# SCH_Main_board_2023-06-05.net
KiCad netlist of a schematic drawn in EasyEDA
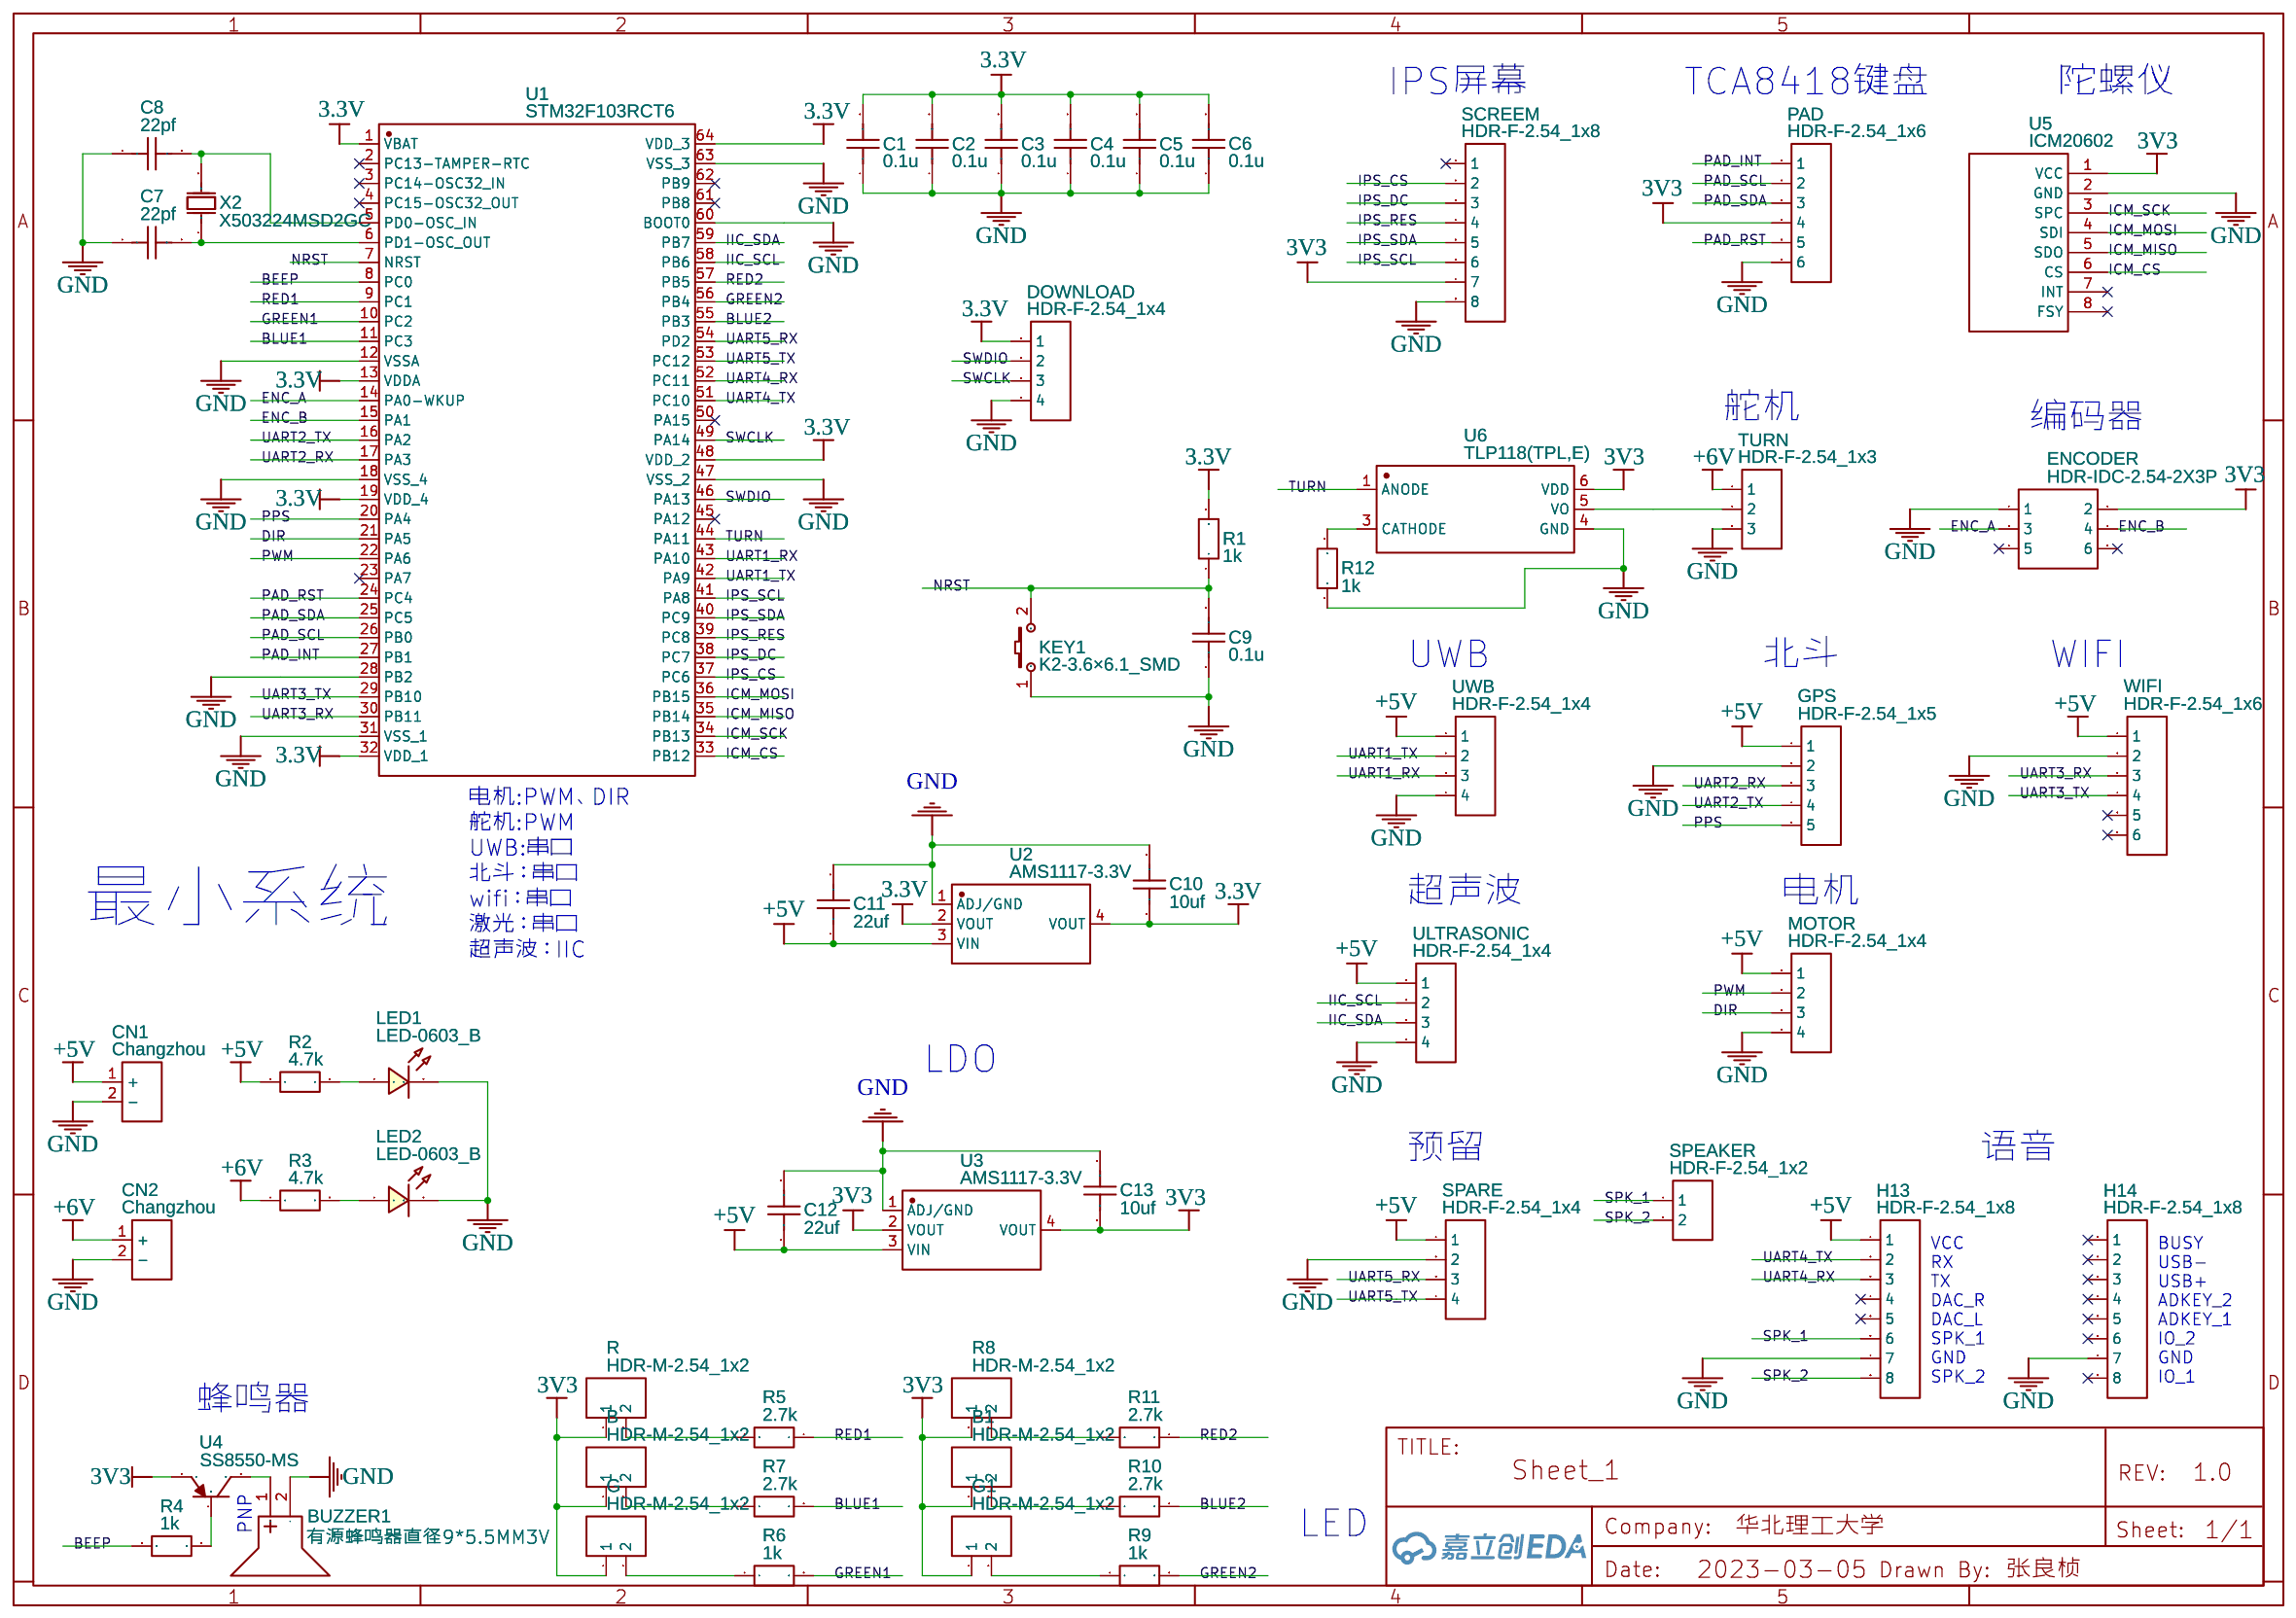
[diagram p0: schematic sheet]

(export (version "E")
  (design (tool "Eeschema 10.0.6"))
  (components
    (comp (ref "B")
      (value "HDR-M-2.54_1x2")
      (fields (field (name "BOM_Supplier Part") "C124375"))
      (libsource (lib "") (part "HDR-M-2.54_1x2_1"))
    )
    (comp (ref "B1")
      (value "HDR-M-2.54_1x2")
      (fields (field (name "BOM_Supplier Part") "C124375"))
      (libsource (lib "") (part "HDR-M-2.54_1x2_1"))
    )
    (comp (ref "BUZZER1")
      (value "有源蜂鸣器直径9*5.5MM3V")
      (fields
        (field (name "BOM_Manufacturer Part") "有源蜂鸣器直径9*5.5mm3V")
        (field (name "BOM_Supplier Part") "C9900012728")
      )
      (libsource (lib "") (part "有源蜂鸣器直径9*5.5MM3V"))
    )
    (comp (ref "C1") (value "0.1u") (libsource (lib "") (part "C_0603_US")))
    (comp (ref "C2") (value "0.1u") (libsource (lib "") (part "C_0603_US")))
    (comp (ref "C3") (value "0.1u") (libsource (lib "") (part "C_0603_US")))
    (comp (ref "C4") (value "0.1u") (libsource (lib "") (part "C_0603_US")))
    (comp (ref "C5") (value "0.1u") (libsource (lib "") (part "C_0603_US")))
    (comp (ref "C6") (value "0.1u") (libsource (lib "") (part "C_0603_US")))
    (comp (ref "C7") (value "22pf") (libsource (lib "") (part "C_0603_US_1")))
    (comp (ref "C8") (value "22pf") (libsource (lib "") (part "C_0603_US_1")))
    (comp (ref "C9") (value "0.1u") (libsource (lib "") (part "C_0603_US")))
    (comp (ref "C10") (value "10uf") (libsource (lib "") (part "C_0805_US")))
    (comp (ref "C11") (value "22uf") (libsource (lib "") (part "C_0805_US_1")))
    (comp (ref "C12") (value "22uf") (libsource (lib "") (part "C_0805_US_1")))
    (comp (ref "C13") (value "10uf") (libsource (lib "") (part "C_0805_US")))
    (comp (ref "CN1")
      (value "Changzhou")
      (fields
        (field (name "BOM_Manufacturer Part") "XT30UPB30-F.G.*")
        (field (name "BOM_Supplier Part") "C108769")
      )
      (libsource (lib "") (part "XT30UPB-F"))
    )
    (comp (ref "CN2")
      (value "Changzhou")
      (fields
        (field (name "BOM_Manufacturer Part") "XT30UPB30-F.G.*")
        (field (name "BOM_Supplier Part") "C108769")
      )
      (libsource (lib "") (part "XT30UPB-F"))
    )
    (comp (ref "DOWNLOAD")
      (value "HDR-F-2.54_1x4")
      (fields (field (name "BOM_Supplier Part") "C225501"))
      (libsource (lib "") (part "HDR-F-2.54_1x4"))
    )
    (comp (ref "ENCODER")
      (value "HDR-IDC-2.54-2X3P")
      (fields
        (field (name "BOM_Manufacturer Part") "2X3 2.54mm IDC Box")
        (field (name "BOM_Supplier Part") "C11214")
      )
      (libsource (lib "") (part "HDR-IDC-2.54-2X3P"))
    )
    (comp (ref "G")
      (value "HDR-M-2.54_1x2")
      (fields (field (name "BOM_Supplier Part") "C124375"))
      (libsource (lib "") (part "HDR-M-2.54_1x2_2"))
    )
    (comp (ref "G1")
      (value "HDR-M-2.54_1x2")
      (fields (field (name "BOM_Supplier Part") "C124375"))
      (libsource (lib "") (part "HDR-M-2.54_1x2_2"))
    )
    (comp (ref "GPS")
      (value "HDR-F-2.54_1x5")
      (fields (field (name "BOM_Supplier Part") "C50950"))
      (libsource (lib "") (part "HDR-F-2.54_1x5"))
    )
    (comp (ref "H13")
      (value "HDR-F-2.54_1x8")
      (fields (field (name "BOM_Supplier Part") "C225505"))
      (libsource (lib "") (part "HDR-F-2.54_1x8_1"))
    )
    (comp (ref "H14")
      (value "HDR-F-2.54_1x8")
      (fields (field (name "BOM_Supplier Part") "C225505"))
      (libsource (lib "") (part "HDR-F-2.54_1x8_1"))
    )
    (comp (ref "KEY1")
      (value "K2-3.6×6.1_SMD")
      (fields
        (field (name "BOM_Manufacturer Part") "K2-1107ST-A4SW-06")
        (field (name "BOM_Supplier Part") "C118141")
      )
      (libsource (lib "") (part "K2-3.6×6.1_SMD"))
    )
    (comp (ref "LED1")
      (value "LED-0603_B")
      (fields
        (field (name "BOM_Manufacturer Part") "19-217/BHC-ZL1M2RY/3T")
        (field (name "BOM_Supplier Part") "C72041")
      )
      (libsource (lib "") (part "LED-0603_B"))
    )
    (comp (ref "LED2")
      (value "LED-0603_B")
      (fields
        (field (name "BOM_Manufacturer Part") "19-217/BHC-ZL1M2RY/3T")
        (field (name "BOM_Supplier Part") "C72041")
      )
      (libsource (lib "") (part "LED-0603_B"))
    )
    (comp (ref "MOTOR")
      (value "HDR-F-2.54_1x4")
      (fields (field (name "BOM_Supplier Part") "C225501"))
      (libsource (lib "") (part "HDR-F-2.54_1x4_4"))
    )
    (comp (ref "PAD")
      (value "HDR-F-2.54_1x6")
      (fields (field (name "BOM_Supplier Part") "C40877"))
      (libsource (lib "") (part "HDR-F-2.54_1x6"))
    )
    (comp (ref "R")
      (value "HDR-M-2.54_1x2")
      (fields (field (name "BOM_Supplier Part") "C124375"))
      (libsource (lib "") (part "HDR-M-2.54_1x2"))
    )
    (comp (ref "R1") (value "1k") (libsource (lib "") (part "R_0603_EU_2")))
    (comp (ref "R2") (value "4.7k") (libsource (lib "") (part "R_0603_EU")))
    (comp (ref "R3") (value "4.7k") (libsource (lib "") (part "R_0603_EU")))
    (comp (ref "R4") (value "1k") (libsource (lib "") (part "R_0603_EU")))
    (comp (ref "R5") (value "2.7k") (libsource (lib "") (part "R_0603_EU_1")))
    (comp (ref "R6") (value "1k") (libsource (lib "") (part "R_0603_EU")))
    (comp (ref "R7") (value "2.7k") (libsource (lib "") (part "R_0603_EU")))
    (comp (ref "R8")
      (value "HDR-M-2.54_1x2")
      (fields (field (name "BOM_Supplier Part") "C124375"))
      (libsource (lib "") (part "HDR-M-2.54_1x2"))
    )
    (comp (ref "R9") (value "1k") (libsource (lib "") (part "R_0603_EU")))
    (comp (ref "R10") (value "2.7k") (libsource (lib "") (part "R_0603_EU")))
    (comp (ref "R11") (value "2.7k") (libsource (lib "") (part "R_0603_EU_1")))
    (comp (ref "R12") (value "1k") (libsource (lib "") (part "R_0603_EU_2")))
    (comp (ref "SCREEM")
      (value "HDR-F-2.54_1x8")
      (fields (field (name "BOM_Supplier Part") "C225505"))
      (libsource (lib "") (part "HDR-F-2.54_1x8"))
    )
    (comp (ref "SPARE")
      (value "HDR-F-2.54_1x4")
      (fields (field (name "BOM_Supplier Part") "C225501"))
      (libsource (lib "") (part "HDR-F-2.54_1x4_3"))
    )
    (comp (ref "SPEAKER")
      (value "HDR-F-2.54_1x2")
      (fields (field (name "BOM_Supplier Part") "C49661"))
      (libsource (lib "") (part "HDR-F-2.54_1x2"))
    )
    (comp (ref "TURN")
      (value "HDR-F-2.54_1x3")
      (fields (field (name "BOM_Supplier Part") "C146690"))
      (libsource (lib "") (part "HDR-F-2.54_1x3"))
    )
    (comp (ref "U1")
      (value "STM32F103RCT6")
      (fields (field (name "BOM_Supplier Part") "C8323"))
      (libsource (lib "") (part "STM32F103RCT6"))
    )
    (comp (ref "U2")
      (value "AMS1117-3.3V")
      (fields (field (name "BOM_Supplier Part") "C2688239"))
      (libsource (lib "") (part "AMS1117-3.3V"))
    )
    (comp (ref "U3")
      (value "AMS1117-3.3V")
      (fields (field (name "BOM_Supplier Part") "C2688239"))
      (libsource (lib "") (part "AMS1117-3.3V"))
    )
    (comp (ref "U4")
      (value "SS8550-MS")
      (fields (field (name "BOM_Supplier Part") "C5120747"))
      (libsource (lib "") (part "SS8550-MS"))
    )
    (comp (ref "U5") (value "ICM20602") (libsource (lib "") (part "ICM20602")))
    (comp (ref "U6")
      (value "TLP118(TPL,E)")
      (fields (field (name "BOM_Supplier Part") "C89721"))
      (libsource (lib "") (part "TLP118(TPL,E)"))
    )
    (comp (ref "ULTRASONIC")
      (value "HDR-F-2.54_1x4")
      (fields (field (name "BOM_Supplier Part") "C225501"))
      (libsource (lib "") (part "HDR-F-2.54_1x4_2"))
    )
    (comp (ref "UWB")
      (value "HDR-F-2.54_1x4")
      (fields (field (name "BOM_Supplier Part") "C225501"))
      (libsource (lib "") (part "HDR-F-2.54_1x4_1"))
    )
    (comp (ref "WIFI")
      (value "HDR-F-2.54_1x6")
      (fields (field (name "BOM_Supplier Part") "C40877"))
      (libsource (lib "") (part "HDR-F-2.54_1x6_1"))
    )
    (comp (ref "X2")
      (value "X503224MSD2GC")
      (fields (field (name "BOM_Supplier Part") "C48304"))
      (libsource (lib "") (part "X503224MSD2GC"))
    )
  )
  (nets
    (net (code "1") (name "+5V") (class "Default")
      (node (ref "C11") (pin "1") (pinfunction "1_1") (pintype "unspecified"))
      (node (ref "C12") (pin "1") (pinfunction "1_1") (pintype "unspecified"))
      (node (ref "CN1") (pin "1") (pinfunction "+_1") (pintype "unspecified"))
      (node (ref "GPS") (pin "1") (pinfunction "1_1") (pintype "unspecified"))
      (node (ref "H13") (pin "1") (pinfunction "1_1") (pintype "unspecified"))
      (node (ref "MOTOR") (pin "1") (pinfunction "1_1") (pintype "unspecified"))
      (node (ref "R2") (pin "1") (pinfunction "1_1") (pintype "unspecified"))
      (node (ref "SPARE") (pin "1") (pinfunction "1_1") (pintype "unspecified"))
      (node (ref "U2") (pin "3") (pinfunction "VIN_3") (pintype "unspecified"))
      (node (ref "U3") (pin "3") (pinfunction "VIN_3") (pintype "unspecified"))
      (node (ref "ULTRASONIC") (pin "1") (pinfunction "1_1") (pintype "unspecified"))
      (node (ref "UWB") (pin "1") (pinfunction "1_1") (pintype "unspecified"))
      (node (ref "WIFI") (pin "1") (pinfunction "1_1") (pintype "input"))
    )
    (net (code "2") (name "+6V") (class "Default")
      (node (ref "CN2") (pin "1") (pinfunction "+_1") (pintype "unspecified"))
      (node (ref "R3") (pin "1") (pinfunction "1_1") (pintype "unspecified"))
      (node (ref "TURN") (pin "1") (pinfunction "1_1") (pintype "input"))
    )
    (net (code "3") (name "/BEEP") (class "Default")
      (node (ref "R4") (pin "1") (pinfunction "1_1") (pintype "unspecified"))
      (node (ref "U1") (pin "8") (pinfunction "PC0_8") (pintype "unspecified"))
    )
    (net (code "4") (name "/BLUE1") (class "Default")
      (node (ref "R7") (pin "2") (pinfunction "2_2") (pintype "unspecified"))
      (node (ref "U1") (pin "11") (pinfunction "PC3_11") (pintype "unspecified"))
    )
    (net (code "5") (name "/BLUE2") (class "Default")
      (node (ref "R10") (pin "2") (pinfunction "2_2") (pintype "unspecified"))
      (node (ref "U1") (pin "55") (pinfunction "PB3_55") (pintype "unspecified"))
    )
    (net (code "6") (name "/DIR") (class "Default")
      (node (ref "MOTOR") (pin "3") (pinfunction "3_3") (pintype "unspecified"))
      (node (ref "U1") (pin "21") (pinfunction "PA5_21") (pintype "unspecified"))
    )
    (net (code "7") (name "/ENC_A") (class "Default")
      (node (ref "ENCODER") (pin "3") (pinfunction "3_3") (pintype "unspecified"))
      (node (ref "U1") (pin "14") (pinfunction "PA0-WKUP_14") (pintype "unspecified"))
    )
    (net (code "8") (name "/ENC_B") (class "Default")
      (node (ref "ENCODER") (pin "4") (pinfunction "4_4") (pintype "unspecified"))
      (node (ref "U1") (pin "15") (pinfunction "PA1_15") (pintype "unspecified"))
    )
    (net (code "9") (name "/GREEN1") (class "Default")
      (node (ref "R6") (pin "2") (pinfunction "2_2") (pintype "unspecified"))
      (node (ref "U1") (pin "10") (pinfunction "PC2_10") (pintype "unspecified"))
    )
    (net (code "10") (name "/GREEN2") (class "Default")
      (node (ref "R9") (pin "2") (pinfunction "2_2") (pintype "unspecified"))
      (node (ref "U1") (pin "56") (pinfunction "PB4_56") (pintype "unspecified"))
    )
    (net (code "11") (name "/ICM_CS") (class "Default")
      (node (ref "U1") (pin "33") (pinfunction "PB12_33") (pintype "unspecified"))
      (node (ref "U5") (pin "6") (pinfunction "CS_6") (pintype "unspecified"))
    )
    (net (code "12") (name "/ICM_MISO") (class "Default")
      (node (ref "U1") (pin "35") (pinfunction "PB14_35") (pintype "unspecified"))
      (node (ref "U5") (pin "5") (pinfunction "SDO_5") (pintype "unspecified"))
    )
    (net (code "13") (name "/ICM_MOSI") (class "Default")
      (node (ref "U1") (pin "36") (pinfunction "PB15_36") (pintype "unspecified"))
      (node (ref "U5") (pin "4") (pinfunction "SDI_4") (pintype "unspecified"))
    )
    (net (code "14") (name "/ICM_SCK") (class "Default")
      (node (ref "U1") (pin "34") (pinfunction "PB13_34") (pintype "unspecified"))
      (node (ref "U5") (pin "3") (pinfunction "SPC_3") (pintype "unspecified"))
    )
    (net (code "15") (name "/IIC_SCL") (class "Default")
      (node (ref "U1") (pin "58") (pinfunction "PB6_58") (pintype "unspecified"))
      (node (ref "ULTRASONIC") (pin "2") (pinfunction "2_2") (pintype "unspecified"))
    )
    (net (code "16") (name "/IIC_SDA") (class "Default")
      (node (ref "U1") (pin "59") (pinfunction "PB7_59") (pintype "unspecified"))
      (node (ref "ULTRASONIC") (pin "3") (pinfunction "3_3") (pintype "unspecified"))
    )
    (net (code "17") (name "/IPS_CS") (class "Default")
      (node (ref "SCREEM") (pin "2") (pinfunction "2_2") (pintype "unspecified"))
      (node (ref "U1") (pin "37") (pinfunction "PC6_37") (pintype "unspecified"))
    )
    (net (code "18") (name "/IPS_DC") (class "Default")
      (node (ref "SCREEM") (pin "3") (pinfunction "3_3") (pintype "unspecified"))
      (node (ref "U1") (pin "38") (pinfunction "PC7_38") (pintype "unspecified"))
    )
    (net (code "19") (name "/IPS_RES") (class "Default")
      (node (ref "SCREEM") (pin "4") (pinfunction "4_4") (pintype "unspecified"))
      (node (ref "U1") (pin "39") (pinfunction "PC8_39") (pintype "unspecified"))
    )
    (net (code "20") (name "/IPS_SCL") (class "Default")
      (node (ref "SCREEM") (pin "6") (pinfunction "6_6") (pintype "unspecified"))
      (node (ref "U1") (pin "41") (pinfunction "PA8_41") (pintype "unspecified"))
    )
    (net (code "21") (name "/IPS_SDA") (class "Default")
      (node (ref "SCREEM") (pin "5") (pinfunction "5_5") (pintype "unspecified"))
      (node (ref "U1") (pin "40") (pinfunction "PC9_40") (pintype "unspecified"))
    )
    (net (code "22") (name "/NRST") (class "Default")
      (node (ref "C9") (pin "2") (pinfunction "2_2") (pintype "unspecified"))
      (node (ref "KEY1") (pin "2") (pinfunction "2_2") (pintype "unspecified"))
      (node (ref "R1") (pin "1") (pinfunction "1_1") (pintype "unspecified"))
      (node (ref "U1") (pin "7") (pinfunction "NRST_7") (pintype "unspecified"))
    )
    (net (code "23") (name "/PAD_INT") (class "Default")
      (node (ref "PAD") (pin "1") (pinfunction "1_1") (pintype "input"))
      (node (ref "U1") (pin "27") (pinfunction "PB1_27") (pintype "unspecified"))
    )
    (net (code "24") (name "/PAD_RST") (class "Default")
      (node (ref "PAD") (pin "5") (pinfunction "5_5") (pintype "input"))
      (node (ref "U1") (pin "24") (pinfunction "PC4_24") (pintype "unspecified"))
    )
    (net (code "25") (name "/PAD_SCL") (class "Default")
      (node (ref "PAD") (pin "2") (pinfunction "2_2") (pintype "input"))
      (node (ref "U1") (pin "26") (pinfunction "PB0_26") (pintype "unspecified"))
    )
    (net (code "26") (name "/PAD_SDA") (class "Default")
      (node (ref "PAD") (pin "3") (pinfunction "3_3") (pintype "input"))
      (node (ref "U1") (pin "25") (pinfunction "PC5_25") (pintype "unspecified"))
    )
    (net (code "27") (name "/PPS") (class "Default")
      (node (ref "GPS") (pin "5") (pinfunction "5_5") (pintype "unspecified"))
      (node (ref "U1") (pin "20") (pinfunction "PA4_20") (pintype "unspecified"))
    )
    (net (code "28") (name "/PWM") (class "Default")
      (node (ref "MOTOR") (pin "2") (pinfunction "2_2") (pintype "unspecified"))
      (node (ref "U1") (pin "22") (pinfunction "PA6_22") (pintype "unspecified"))
    )
    (net (code "29") (name "/RED1") (class "Default")
      (node (ref "R5") (pin "1") (pinfunction "1_1") (pintype "unspecified"))
      (node (ref "U1") (pin "9") (pinfunction "PC1_9") (pintype "unspecified"))
    )
    (net (code "30") (name "/RED2") (class "Default")
      (node (ref "R11") (pin "1") (pinfunction "1_1") (pintype "unspecified"))
      (node (ref "U1") (pin "57") (pinfunction "PB5_57") (pintype "unspecified"))
    )
    (net (code "31") (name "/SPK_1") (class "Default")
      (node (ref "H13") (pin "6") (pinfunction "6_6") (pintype "unspecified"))
      (node (ref "SPEAKER") (pin "1") (pinfunction "1_1") (pintype "input"))
    )
    (net (code "32") (name "/SPK_2") (class "Default")
      (node (ref "H13") (pin "8") (pinfunction "8_8") (pintype "unspecified"))
      (node (ref "SPEAKER") (pin "2") (pinfunction "2_2") (pintype "input"))
    )
    (net (code "33") (name "/SWCLK") (class "Default")
      (node (ref "DOWNLOAD") (pin "3") (pinfunction "3_3") (pintype "unspecified"))
      (node (ref "U1") (pin "49") (pinfunction "PA14_49") (pintype "unspecified"))
    )
    (net (code "34") (name "/SWDIO") (class "Default")
      (node (ref "DOWNLOAD") (pin "2") (pinfunction "2_2") (pintype "unspecified"))
      (node (ref "U1") (pin "46") (pinfunction "PA13_46") (pintype "unspecified"))
    )
    (net (code "35") (name "/TURN") (class "Default")
      (node (ref "U1") (pin "44") (pinfunction "PA11_44") (pintype "unspecified"))
      (node (ref "U6") (pin "1") (pinfunction "ANODE_1") (pintype "unspecified"))
    )
    (net (code "36") (name "/UART1_RX") (class "Default")
      (node (ref "U1") (pin "43") (pinfunction "PA10_43") (pintype "unspecified"))
      (node (ref "UWB") (pin "3") (pinfunction "3_3") (pintype "unspecified"))
    )
    (net (code "37") (name "/UART1_TX") (class "Default")
      (node (ref "U1") (pin "42") (pinfunction "PA9_42") (pintype "unspecified"))
      (node (ref "UWB") (pin "2") (pinfunction "2_2") (pintype "unspecified"))
    )
    (net (code "38") (name "/UART2_RX") (class "Default")
      (node (ref "GPS") (pin "3") (pinfunction "3_3") (pintype "unspecified"))
      (node (ref "U1") (pin "17") (pinfunction "PA3_17") (pintype "unspecified"))
    )
    (net (code "39") (name "/UART2_TX") (class "Default")
      (node (ref "GPS") (pin "4") (pinfunction "4_4") (pintype "unspecified"))
      (node (ref "U1") (pin "16") (pinfunction "PA2_16") (pintype "unspecified"))
    )
    (net (code "40") (name "/UART3_RX") (class "Default")
      (node (ref "U1") (pin "30") (pinfunction "PB11_30") (pintype "unspecified"))
      (node (ref "WIFI") (pin "3") (pinfunction "3_3") (pintype "input"))
    )
    (net (code "41") (name "/UART3_TX") (class "Default")
      (node (ref "U1") (pin "29") (pinfunction "PB10_29") (pintype "unspecified"))
      (node (ref "WIFI") (pin "4") (pinfunction "4_4") (pintype "input"))
    )
    (net (code "42") (name "/UART4_RX") (class "Default")
      (node (ref "H13") (pin "3") (pinfunction "3_3") (pintype "unspecified"))
      (node (ref "U1") (pin "52") (pinfunction "PC11_52") (pintype "unspecified"))
    )
    (net (code "43") (name "/UART4_TX") (class "Default")
      (node (ref "H13") (pin "2") (pinfunction "2_2") (pintype "unspecified"))
      (node (ref "U1") (pin "51") (pinfunction "PC10_51") (pintype "unspecified"))
    )
    (net (code "44") (name "/UART5_RX") (class "Default")
      (node (ref "SPARE") (pin "3") (pinfunction "3_3") (pintype "unspecified"))
      (node (ref "U1") (pin "54") (pinfunction "PD2_54") (pintype "unspecified"))
    )
    (net (code "45") (name "/UART5_TX") (class "Default")
      (node (ref "SPARE") (pin "4") (pinfunction "4_4") (pintype "unspecified"))
      (node (ref "U1") (pin "53") (pinfunction "PC12_53") (pintype "unspecified"))
    )
    (net (code "46") (name "3.3V") (class "Default")
      (node (ref "C1") (pin "2") (pinfunction "2_2") (pintype "unspecified"))
      (node (ref "C10") (pin "2") (pinfunction "2_2") (pintype "unspecified"))
      (node (ref "C2") (pin "2") (pinfunction "2_2") (pintype "unspecified"))
      (node (ref "C3") (pin "2") (pinfunction "2_2") (pintype "unspecified"))
      (node (ref "C4") (pin "2") (pinfunction "2_2") (pintype "unspecified"))
      (node (ref "C5") (pin "2") (pinfunction "2_2") (pintype "unspecified"))
      (node (ref "C6") (pin "2") (pinfunction "2_2") (pintype "unspecified"))
      (node (ref "DOWNLOAD") (pin "1") (pinfunction "1_1") (pintype "unspecified"))
      (node (ref "R1") (pin "2") (pinfunction "2_2") (pintype "unspecified"))
      (node (ref "U1") (pin "1") (pinfunction "VBAT_1") (pintype "unspecified"))
      (node (ref "U1") (pin "13") (pinfunction "VDDA_13") (pintype "unspecified"))
      (node (ref "U1") (pin "19") (pinfunction "VDD_4_19") (pintype "unspecified"))
      (node (ref "U1") (pin "32") (pinfunction "VDD_1_32") (pintype "unspecified"))
      (node (ref "U1") (pin "48") (pinfunction "VDD_2_48") (pintype "unspecified"))
      (node (ref "U1") (pin "64") (pinfunction "VDD_3_64") (pintype "unspecified"))
      (node (ref "U2") (pin "2") (pinfunction "VOUT_2") (pintype "unspecified"))
      (node (ref "U2") (pin "4") (pinfunction "VOUT_4") (pintype "unspecified"))
    )
    (net (code "47") (name "3V3") (class "Default")
      (node (ref "B") (pin "1") (pinfunction "1_1") (pintype "unspecified"))
      (node (ref "B1") (pin "1") (pinfunction "1_1") (pintype "unspecified"))
      (node (ref "C13") (pin "2") (pinfunction "2_2") (pintype "unspecified"))
      (node (ref "ENCODER") (pin "2") (pinfunction "2_2") (pintype "unspecified"))
      (node (ref "G") (pin "1") (pinfunction "1_1") (pintype "unspecified"))
      (node (ref "G1") (pin "1") (pinfunction "1_1") (pintype "unspecified"))
      (node (ref "PAD") (pin "4") (pinfunction "4_4") (pintype "input"))
      (node (ref "R") (pin "1") (pinfunction "1_1") (pintype "unspecified"))
      (node (ref "R8") (pin "1") (pinfunction "1_1") (pintype "unspecified"))
      (node (ref "SCREEM") (pin "7") (pinfunction "7_7") (pintype "unspecified"))
      (node (ref "U3") (pin "2") (pinfunction "VOUT_2") (pintype "unspecified"))
      (node (ref "U3") (pin "4") (pinfunction "VOUT_4") (pintype "unspecified"))
      (node (ref "U4") (pin "2") (pinfunction "E_2") (pintype "input"))
      (node (ref "U5") (pin "1") (pinfunction "VCC_1") (pintype "unspecified"))
      (node (ref "U6") (pin "6") (pinfunction "VDD_6") (pintype "unspecified"))
    )
    (net (code "48") (name "GND") (class "Default")
      (node (ref "BUZZER1") (pin "2") (pinfunction "-_2") (pintype "unspecified"))
      (node (ref "C1") (pin "1") (pinfunction "1_1") (pintype "unspecified"))
      (node (ref "C10") (pin "1") (pinfunction "1_1") (pintype "unspecified"))
      (node (ref "C11") (pin "2") (pinfunction "2_2") (pintype "unspecified"))
      (node (ref "C12") (pin "2") (pinfunction "2_2") (pintype "unspecified"))
      (node (ref "C13") (pin "1") (pinfunction "1_1") (pintype "unspecified"))
      (node (ref "C2") (pin "1") (pinfunction "1_1") (pintype "unspecified"))
      (node (ref "C3") (pin "1") (pinfunction "1_1") (pintype "unspecified"))
      (node (ref "C4") (pin "1") (pinfunction "1_1") (pintype "unspecified"))
      (node (ref "C5") (pin "1") (pinfunction "1_1") (pintype "unspecified"))
      (node (ref "C6") (pin "1") (pinfunction "1_1") (pintype "unspecified"))
      (node (ref "C7") (pin "1") (pinfunction "1_1") (pintype "unspecified"))
      (node (ref "C8") (pin "1") (pinfunction "1_1") (pintype "unspecified"))
      (node (ref "C9") (pin "1") (pinfunction "1_1") (pintype "unspecified"))
      (node (ref "CN1") (pin "2") (pinfunction "-_2") (pintype "unspecified"))
      (node (ref "CN2") (pin "2") (pinfunction "-_2") (pintype "unspecified"))
      (node (ref "DOWNLOAD") (pin "4") (pinfunction "4_4") (pintype "unspecified"))
      (node (ref "ENCODER") (pin "1") (pinfunction "1_1") (pintype "unspecified"))
      (node (ref "GPS") (pin "2") (pinfunction "2_2") (pintype "unspecified"))
      (node (ref "H13") (pin "7") (pinfunction "7_7") (pintype "unspecified"))
      (node (ref "H14") (pin "7") (pinfunction "7_7") (pintype "unspecified"))
      (node (ref "KEY1") (pin "1") (pinfunction "1_1") (pintype "unspecified"))
      (node (ref "LED1") (pin "2") (pinfunction "2_2") (pintype "unspecified"))
      (node (ref "LED2") (pin "2") (pinfunction "2_2") (pintype "unspecified"))
      (node (ref "MOTOR") (pin "4") (pinfunction "4_4") (pintype "unspecified"))
      (node (ref "PAD") (pin "6") (pinfunction "6_6") (pintype "input"))
      (node (ref "R12") (pin "1") (pinfunction "1_1") (pintype "unspecified"))
      (node (ref "SCREEM") (pin "8") (pinfunction "8_8") (pintype "unspecified"))
      (node (ref "SPARE") (pin "2") (pinfunction "2_2") (pintype "unspecified"))
      (node (ref "TURN") (pin "3") (pinfunction "3_3") (pintype "input"))
      (node (ref "U1") (pin "12") (pinfunction "VSSA_12") (pintype "unspecified"))
      (node (ref "U1") (pin "18") (pinfunction "VSS_4_18") (pintype "unspecified"))
      (node (ref "U1") (pin "28") (pinfunction "PB2_28") (pintype "unspecified"))
      (node (ref "U1") (pin "31") (pinfunction "VSS_1_31") (pintype "unspecified"))
      (node (ref "U1") (pin "47") (pinfunction "VSS_2_47") (pintype "unspecified"))
      (node (ref "U1") (pin "60") (pinfunction "BOOT0_60") (pintype "unspecified"))
      (node (ref "U1") (pin "63") (pinfunction "VSS_3_63") (pintype "unspecified"))
      (node (ref "U2") (pin "1") (pinfunction "ADJ/GND_1") (pintype "unspecified"))
      (node (ref "U3") (pin "1") (pinfunction "ADJ/GND_1") (pintype "unspecified"))
      (node (ref "U5") (pin "2") (pinfunction "GND_2") (pintype "unspecified"))
      (node (ref "U6") (pin "4") (pinfunction "GND_4") (pintype "unspecified"))
      (node (ref "ULTRASONIC") (pin "4") (pinfunction "4_4") (pintype "unspecified"))
      (node (ref "UWB") (pin "4") (pinfunction "4_4") (pintype "unspecified"))
      (node (ref "WIFI") (pin "2") (pinfunction "2_2") (pintype "input"))
    )
    (net (code "49") (name "Net-(B-Pad2)") (class "Default")
      (node (ref "B") (pin "2") (pinfunction "2_2") (pintype "unspecified"))
      (node (ref "R7") (pin "1") (pinfunction "1_1") (pintype "unspecified"))
    )
    (net (code "50") (name "Net-(B1-Pad2)") (class "Default")
      (node (ref "B1") (pin "2") (pinfunction "2_2") (pintype "unspecified"))
      (node (ref "R10") (pin "1") (pinfunction "1_1") (pintype "unspecified"))
    )
    (net (code "51") (name "Net-(BUZZER1-+)") (class "Default")
      (node (ref "BUZZER1") (pin "1") (pinfunction "+_1") (pintype "unspecified"))
      (node (ref "U4") (pin "3") (pinfunction "C_3") (pintype "input"))
    )
    (net (code "52") (name "Net-(G-Pad2)") (class "Default")
      (node (ref "G") (pin "2") (pinfunction "2_2") (pintype "unspecified"))
      (node (ref "R6") (pin "1") (pinfunction "1_1") (pintype "unspecified"))
    )
    (net (code "53") (name "Net-(G1-Pad2)") (class "Default")
      (node (ref "G1") (pin "2") (pinfunction "2_2") (pintype "unspecified"))
      (node (ref "R9") (pin "1") (pinfunction "1_1") (pintype "unspecified"))
    )
    (net (code "54") (name "Net-(LED1-Pad1)") (class "Default")
      (node (ref "LED1") (pin "1") (pinfunction "1_1") (pintype "unspecified"))
      (node (ref "R2") (pin "2") (pinfunction "2_2") (pintype "unspecified"))
    )
    (net (code "55") (name "Net-(LED2-Pad1)") (class "Default")
      (node (ref "LED2") (pin "1") (pinfunction "1_1") (pintype "unspecified"))
      (node (ref "R3") (pin "2") (pinfunction "2_2") (pintype "unspecified"))
    )
    (net (code "56") (name "Net-(R-Pad2)") (class "Default")
      (node (ref "R") (pin "2") (pinfunction "2_2") (pintype "unspecified"))
      (node (ref "R5") (pin "2") (pinfunction "2_2") (pintype "unspecified"))
    )
    (net (code "57") (name "Net-(R11-Pad2)") (class "Default")
      (node (ref "R11") (pin "2") (pinfunction "2_2") (pintype "unspecified"))
      (node (ref "R8") (pin "2") (pinfunction "2_2") (pintype "unspecified"))
    )
    (net (code "58") (name "Net-(U1-PD0-OSC_IN)") (class "Default")
      (node (ref "C8") (pin "2") (pinfunction "2_2") (pintype "unspecified"))
      (node (ref "U1") (pin "5") (pinfunction "PD0-OSC_IN_5") (pintype "unspecified"))
      (node (ref "X2") (pin "2") (pinfunction "OSC2_2") (pintype "input"))
    )
    (net (code "59") (name "Net-(U1-PD1-OSC_OUT)") (class "Default")
      (node (ref "C7") (pin "2") (pinfunction "2_2") (pintype "unspecified"))
      (node (ref "U1") (pin "6") (pinfunction "PD1-OSC_OUT_6") (pintype "unspecified"))
      (node (ref "X2") (pin "1") (pinfunction "OSC1_1") (pintype "input"))
    )
    (net (code "60") (name "Net-(U4-B)") (class "Default")
      (node (ref "R4") (pin "2") (pinfunction "2_2") (pintype "unspecified"))
      (node (ref "U4") (pin "1") (pinfunction "B_1") (pintype "input"))
    )
    (net (code "61") (name "Net-(U6-CATHODE)") (class "Default")
      (node (ref "R12") (pin "2") (pinfunction "2_2") (pintype "unspecified"))
      (node (ref "U6") (pin "3") (pinfunction "CATHODE_3") (pintype "unspecified"))
    )
    (net (code "62") (name "Net-(U6-VO)") (class "Default")
      (node (ref "TURN") (pin "2") (pinfunction "2_2") (pintype "input"))
      (node (ref "U6") (pin "5") (pinfunction "VO_5") (pintype "unspecified"))
    )
    (net (code "63") (name "unconnected-(ENCODER-Pad5)") (class "Default")
      (node (ref "ENCODER") (pin "5") (pinfunction "5_5") (pintype "unspecified+no_connect"))
    )
    (net (code "64") (name "unconnected-(ENCODER-Pad6)") (class "Default")
      (node (ref "ENCODER") (pin "6") (pinfunction "6_6") (pintype "unspecified+no_connect"))
    )
    (net (code "65") (name "unconnected-(H13-Pad4)") (class "Default")
      (node (ref "H13") (pin "4") (pinfunction "4_4") (pintype "unspecified+no_connect"))
    )
    (net (code "66") (name "unconnected-(H13-Pad5)") (class "Default")
      (node (ref "H13") (pin "5") (pinfunction "5_5") (pintype "unspecified+no_connect"))
    )
    (net (code "67") (name "unconnected-(H14-Pad1)") (class "Default")
      (node (ref "H14") (pin "1") (pinfunction "1_1") (pintype "unspecified+no_connect"))
    )
    (net (code "68") (name "unconnected-(H14-Pad2)") (class "Default")
      (node (ref "H14") (pin "2") (pinfunction "2_2") (pintype "unspecified+no_connect"))
    )
    (net (code "69") (name "unconnected-(H14-Pad3)") (class "Default")
      (node (ref "H14") (pin "3") (pinfunction "3_3") (pintype "unspecified+no_connect"))
    )
    (net (code "70") (name "unconnected-(H14-Pad4)") (class "Default")
      (node (ref "H14") (pin "4") (pinfunction "4_4") (pintype "unspecified+no_connect"))
    )
    (net (code "71") (name "unconnected-(H14-Pad5)") (class "Default")
      (node (ref "H14") (pin "5") (pinfunction "5_5") (pintype "unspecified+no_connect"))
    )
    (net (code "72") (name "unconnected-(H14-Pad6)") (class "Default")
      (node (ref "H14") (pin "6") (pinfunction "6_6") (pintype "unspecified+no_connect"))
    )
    (net (code "73") (name "unconnected-(H14-Pad8)") (class "Default")
      (node (ref "H14") (pin "8") (pinfunction "8_8") (pintype "unspecified+no_connect"))
    )
    (net (code "74") (name "unconnected-(SCREEM-Pad1)") (class "Default")
      (node (ref "SCREEM") (pin "1") (pinfunction "1_1") (pintype "unspecified+no_connect"))
    )
    (net (code "75") (name "unconnected-(U1-PA7-Pad23)") (class "Default")
      (node (ref "U1") (pin "23") (pinfunction "PA7_23") (pintype "unspecified+no_connect"))
    )
    (net (code "76") (name "unconnected-(U1-PA12-Pad45)") (class "Default")
      (node (ref "U1") (pin "45") (pinfunction "PA12_45") (pintype "unspecified+no_connect"))
    )
    (net (code "77") (name "unconnected-(U1-PA15-Pad50)") (class "Default")
      (node (ref "U1") (pin "50") (pinfunction "PA15_50") (pintype "unspecified+no_connect"))
    )
    (net (code "78") (name "unconnected-(U1-PB8-Pad61)") (class "Default")
      (node (ref "U1") (pin "61") (pinfunction "PB8_61") (pintype "unspecified+no_connect"))
    )
    (net (code "79") (name "unconnected-(U1-PB9-Pad62)") (class "Default")
      (node (ref "U1") (pin "62") (pinfunction "PB9_62") (pintype "unspecified+no_connect"))
    )
    (net (code "80") (name "unconnected-(U1-PC13-TAMPER-RTC-Pad2)") (class "Default")
      (node (ref "U1") (pin "2") (pinfunction "PC13-TAMPER-RTC_2") (pintype "unspecified+no_connect"))
    )
    (net (code "81") (name "unconnected-(U1-PC14-OSC32_IN-Pad3)") (class "Default")
      (node (ref "U1") (pin "3") (pinfunction "PC14-OSC32_IN_3") (pintype "unspecified+no_connect"))
    )
    (net (code "82") (name "unconnected-(U1-PC15-OSC32_OUT-Pad4)") (class "Default")
      (node (ref "U1") (pin "4") (pinfunction "PC15-OSC32_OUT_4") (pintype "unspecified+no_connect"))
    )
    (net (code "83") (name "unconnected-(U5-FSY-Pad8)") (class "Default")
      (node (ref "U5") (pin "8") (pinfunction "FSY_8") (pintype "unspecified+no_connect"))
    )
    (net (code "84") (name "unconnected-(U5-INT-Pad7)") (class "Default")
      (node (ref "U5") (pin "7") (pinfunction "INT_7") (pintype "unspecified+no_connect"))
    )
    (net (code "85") (name "unconnected-(WIFI-Pad5)") (class "Default")
      (node (ref "WIFI") (pin "5") (pinfunction "5_5") (pintype "input+no_connect"))
    )
    (net (code "86") (name "unconnected-(WIFI-Pad6)") (class "Default")
      (node (ref "WIFI") (pin "6") (pinfunction "6_6") (pintype "input+no_connect"))
    )
  )
)
